# PowerPCB.net
KiCad netlist of a schematic drawn in Altium Designer
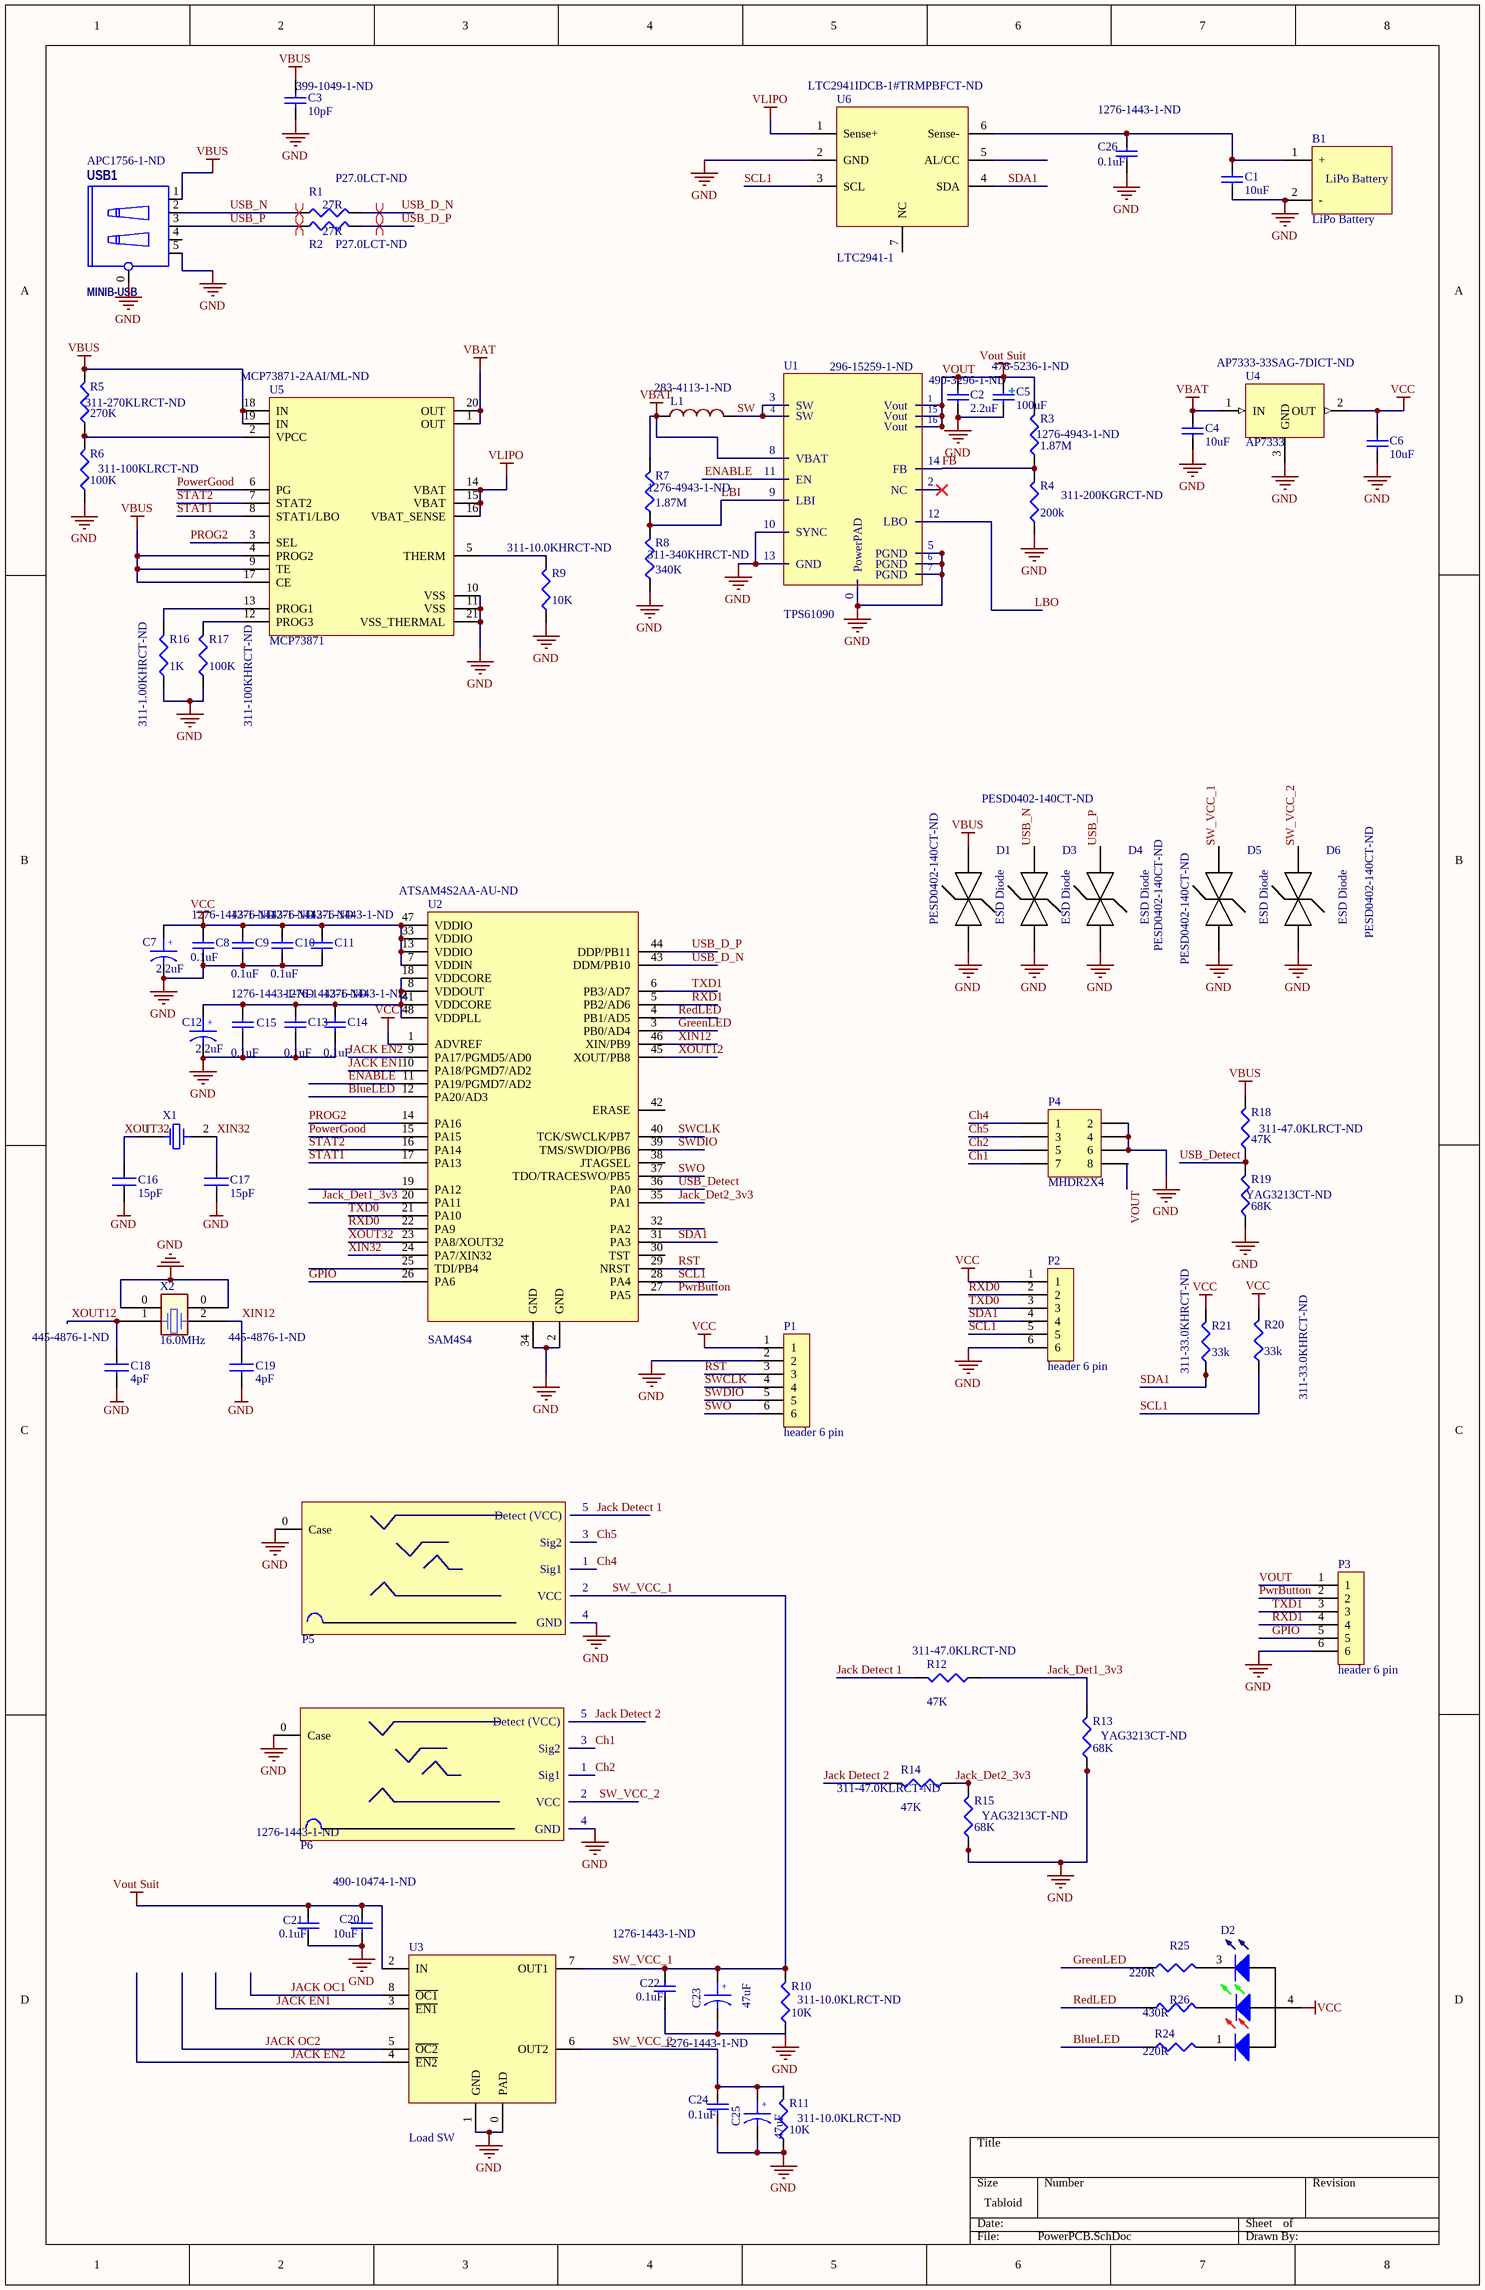
[diagram p0: PowerPCB.SchDoc]

(export (version "E")
  (design (tool "Eeschema 10.0.6"))
  (components
    (comp (ref "B1")
      (value "LiPo Battery")
      (footprint "LiPo Battery")
      (libsource (lib "SenaCorpLibSCH") (part "LiPo Battery"))
    )
    (comp (ref "C1")
      (value "10uF")
      (footprint "0603_small")
      (fields
        (field (name "MANUFACTURER PART NUMBER") "GRM188R61C106MA73D")
        (field (name "MANUFACTURER") "Murata Electronics North America")
        (field (name "TOLERANCE") "±20%")
      )
      (libsource (lib "SenaCorpLibSCH") (part "Cap"))
    )
    (comp (ref "C2")
      (value "2.2uF")
      (footprint "0603_small")
      (fields
        (field (name "SUPPLIER PART NUMBER") "490-3296-1-ND")
        (field (name "MANUFACTURER") "Murata Electronics North America")
        (field (name "TOLERANCE") "±10%")
        (field (name "MANUFACTURER PART NUMBER") "GRM188R61C225KE15D")
      )
      (libsource (lib "SenaCorpLibSCH") (part "Cap"))
    )
    (comp (ref "C3")
      (value "10pF")
      (footprint "0603_small")
      (fields
        (field (name "MANUFACTURER PART NUMBER") "C0603C100J5GACTU")
        (field (name "SUPPLIER PART NUMBER") "399-1049-1-ND")
      )
      (libsource (lib "SenaCorpLibSCH") (part "Cap"))
    )
    (comp (ref "C4")
      (value "10uF")
      (footprint "0603_small")
      (fields
        (field (name "MANUFACTURER PART NUMBER") "GRM188R61C106MA73D")
        (field (name "MANUFACTURER") "Murata Electronics North America")
        (field (name "TOLERANCE") "±20%")
      )
      (libsource (lib "SenaCorpLibSCH") (part "Cap"))
    )
    (comp (ref "C5")
      (value "100uF")
      (footprint "C 6032-28R")
      (description "Capacitor")
      (fields
        (field (name "MANUFACTURER PART NUMBER") "TPSC107M010R0075")
        (field (name "MANUFACTURER") "AVX Corporation")
        (field (name "SUPPLIER PART NUMBER") "478-5236-1-ND")
      )
      (libsource (lib "SenaCorpLibSCH") (part "Cap_Tant"))
    )
    (comp (ref "C6")
      (value "10uF")
      (footprint "0603_small")
      (fields
        (field (name "MANUFACTURER PART NUMBER") "GRM188R61C106MA73D")
        (field (name "MANUFACTURER") "Murata Electronics North America")
        (field (name "TOLERANCE") "±20%")
      )
      (libsource (lib "SenaCorpLibSCH") (part "Cap"))
    )
    (comp (ref "C7")
      (value "2.2uF")
      (footprint "SMD0805")
      (fields
        (field (name "TOLERANCE") "±20%")
        (field (name "MANUFACTURER") "AVX Corporation")
        (field (name "MANUFACTURER PART NUMBER") "F921A225MPA")
      )
      (libsource (lib "AltiumDbLib") (part "CAP-POL"))
    )
    (comp (ref "C8")
      (value "0.1uF")
      (footprint "0402")
      (description "Capacitor")
      (fields
        (field (name "SUPPLIER PART NUMBER") "1276-1443-1-ND")
        (field (name "MANUFACTURER PART NUMBER") "CL05A104MP5NNNC")
        (field (name "TOLERANCE") "±20%")
      )
      (libsource (lib "SenaCorpLibSCH") (part "Cap"))
    )
    (comp (ref "C9")
      (value "0.1uF")
      (footprint "0402")
      (description "Capacitor")
      (fields
        (field (name "SUPPLIER PART NUMBER") "1276-1443-1-ND")
        (field (name "MANUFACTURER PART NUMBER") "CL05A104MP5NNNC")
        (field (name "TOLERANCE") "±20%")
      )
      (libsource (lib "SenaCorpLibSCH") (part "Cap"))
    )
    (comp (ref "C10")
      (value "0.1uF")
      (footprint "0402")
      (description "Capacitor")
      (fields
        (field (name "SUPPLIER PART NUMBER") "1276-1443-1-ND")
        (field (name "MANUFACTURER PART NUMBER") "CL05A104MP5NNNC")
        (field (name "TOLERANCE") "±20%")
      )
      (libsource (lib "SenaCorpLibSCH") (part "Cap"))
    )
    (comp (ref "C11")
      (value "~")
      (footprint "0402")
      (description "Capacitor")
      (fields
        (field (name "SUPPLIER PART NUMBER") "1276-1443-1-ND")
        (field (name "MANUFACTURER PART NUMBER") "CL05A104MP5NNNC")
        (field (name "TOLERANCE") "±20%")
      )
      (libsource (lib "SenaCorpLibSCH") (part "Cap"))
    )
    (comp (ref "C12")
      (value "2.2uF")
      (footprint "SMD0805")
      (fields
        (field (name "TOLERANCE") "±20%")
        (field (name "MANUFACTURER") "AVX Corporation")
        (field (name "MANUFACTURER PART NUMBER") "F921A225MPA")
      )
      (libsource (lib "AltiumDbLib") (part "CAP-POL"))
    )
    (comp (ref "C13")
      (value "0.1uF")
      (footprint "0402")
      (description "Capacitor")
      (fields
        (field (name "SUPPLIER PART NUMBER") "1276-1443-1-ND")
        (field (name "MANUFACTURER PART NUMBER") "CL05A104MP5NNNC")
        (field (name "TOLERANCE") "±20%")
      )
      (libsource (lib "SenaCorpLibSCH") (part "Cap"))
    )
    (comp (ref "C14")
      (value "0.1uF")
      (footprint "0402")
      (description "Capacitor")
      (fields
        (field (name "SUPPLIER PART NUMBER") "1276-1443-1-ND")
        (field (name "MANUFACTURER PART NUMBER") "CL05A104MP5NNNC")
        (field (name "TOLERANCE") "±20%")
      )
      (libsource (lib "SenaCorpLibSCH") (part "Cap"))
    )
    (comp (ref "C15")
      (value "0.1uF")
      (footprint "0402")
      (description "Capacitor")
      (fields
        (field (name "SUPPLIER PART NUMBER") "1276-1443-1-ND")
        (field (name "MANUFACTURER PART NUMBER") "CL05A104MP5NNNC")
        (field (name "TOLERANCE") "±20%")
      )
      (libsource (lib "SenaCorpLibSCH") (part "Cap"))
    )
    (comp (ref "C16")
      (value "15pF")
      (footprint "CAP 0402")
      (fields
        (field (name "TOLERANCE") "±5%")
        (field (name "MANUFACTURER PART NUMBER") "GJM1555C1H150JB01D")
        (field (name "MANUFACTURER") "Murata Electronics North America")
      )
      (libsource (lib "AltiumDbLib") (part "CAP-NONPOL"))
    )
    (comp (ref "C17")
      (value "15pF")
      (footprint "CAP 0402")
      (fields
        (field (name "TOLERANCE") "±5%")
        (field (name "MANUFACTURER PART NUMBER") "GJM1555C1H150JB01D")
        (field (name "MANUFACTURER") "Murata Electronics North America")
      )
      (libsource (lib "AltiumDbLib") (part "CAP-NONPOL"))
    )
    (comp (ref "C18")
      (value "4pF")
      (footprint "0402")
      (fields
        (field (name "MANUFACTURER PART NUMBER") "C1005C0G1H040B050BA")
        (field (name "MANUFACTURER") "TDK Corporation")
        (field (name "SUPPLIER PART NUMBER") "445-4876-1-ND")
        (field (name "TOLERANCE") "±0.1pF")
      )
      (libsource (lib "AltiumDbLib") (part "CAP-NONPOL"))
    )
    (comp (ref "C19")
      (value "4pF")
      (footprint "0402")
      (fields
        (field (name "MANUFACTURER PART NUMBER") "C1005C0G1H040B050BA")
        (field (name "MANUFACTURER") "TDK Corporation")
        (field (name "SUPPLIER PART NUMBER") "445-4876-1-ND")
        (field (name "TOLERANCE") "±0.1pF")
      )
      (libsource (lib "AltiumDbLib") (part "CAP-NONPOL"))
    )
    (comp (ref "C20")
      (value "10uF")
      (footprint "0603_small")
      (fields
        (field (name "MANUFACTURER") "Murata Electronics North America")
        (field (name "MANUFACTURER PART NUMBER") "GRM188R61A106KE69D")
        (field (name "TOLERANCE") "±10%")
        (field (name "SUPPLIER PART NUMBER") "490-10474-1-ND")
      )
      (libsource (lib "SenaCorpLibSCH") (part "Cap"))
    )
    (comp (ref "C21")
      (value "0.1uF")
      (footprint "0402")
      (fields
        (field (name "SUPPLIER PART NUMBER") "1276-1443-1-ND")
        (field (name "MANUFACTURER PART NUMBER") "CL05A104MP5NNNC")
        (field (name "TOLERANCE") "±20%")
        (field (name "MANUFACTURER") "Samsung Electro-Mechanics America, Inc.")
      )
      (libsource (lib "SenaCorpLibSCH") (part "Cap"))
    )
    (comp (ref "C22")
      (value "0.1uF")
      (footprint "0402")
      (fields
        (field (name "SUPPLIER PART NUMBER") "1276-1443-1-ND")
        (field (name "MANUFACTURER PART NUMBER") "CL05A104MP5NNNC")
        (field (name "TOLERANCE") "±20%")
        (field (name "MANUFACTURER") "Samsung Electro-Mechanics America, Inc.")
      )
      (libsource (lib "SenaCorpLibSCH") (part "Cap"))
    )
    (comp (ref "C23")
      (value "47uF")
      (footprint "1206")
      (fields
        (field (name "MANUFACTURER PART NUMBER") "TPSB476K010R0250")
        (field (name "MANUFACTURER") "AVX Corporation")
        (field (name "TOLERANCE") "±10%")
      )
      (libsource (lib "AltiumDbLib") (part "CAP-POL"))
    )
    (comp (ref "C24")
      (value "0.1uF")
      (footprint "0402")
      (fields
        (field (name "SUPPLIER PART NUMBER") "1276-1443-1-ND")
        (field (name "MANUFACTURER PART NUMBER") "CL05A104MP5NNNC")
        (field (name "TOLERANCE") "±20%")
        (field (name "MANUFACTURER") "Samsung Electro-Mechanics America, Inc.")
      )
      (libsource (lib "SenaCorpLibSCH") (part "Cap"))
    )
    (comp (ref "C25")
      (value "47uF")
      (footprint "1206")
      (fields
        (field (name "MANUFACTURER PART NUMBER") "TPSB476K010R0250")
        (field (name "MANUFACTURER") "AVX Corporation")
        (field (name "TOLERANCE") "±10%")
      )
      (libsource (lib "AltiumDbLib") (part "CAP-POL"))
    )
    (comp (ref "C26")
      (value "0.1uF")
      (footprint "0402")
      (fields
        (field (name "SUPPLIER PART NUMBER") "1276-1443-1-ND")
        (field (name "MANUFACTURER PART NUMBER") "CL05A104MP5NNNC")
        (field (name "TOLERANCE") "±20%")
        (field (name "MANUFACTURER") "Samsung Electro-Mechanics America, Inc.")
      )
      (libsource (lib "SenaCorpLibSCH") (part "Cap"))
    )
    (comp (ref "D1")
      (value "ESD Diode")
      (footprint "0402")
      (fields
        (field (name "MANUFACTURER PART NUMBER") "PESD0402-140")
        (field (name "MANUFACTURER") "TE Connectivity Raychem Circuit Protection")
        (field (name "SUPPLIER PART NUMBER") "PESD0402-140CT-ND")
      )
      (libsource (lib "SenaCorpLibSCH") (part "ESD Diode"))
    )
    (comp (ref "D2")
      (value "LED2_RGB")
      (footprint "LED RGB")
      (description "RGB Led")
      (fields
        (field (name "MANUFACTURER PART NUMBER") "LTST-C19HE1WT")
        (field (name "MANUFACTURER") "Lite-On Inc")
      )
      (libsource (lib "SenaCorpLibSCH") (part "LED2_RGB"))
    )
    (comp (ref "D3")
      (value "ESD Diode")
      (footprint "0402")
      (fields
        (field (name "MANUFACTURER PART NUMBER") "PESD0402-140")
        (field (name "MANUFACTURER") "TE Connectivity Raychem Circuit Protection")
        (field (name "SUPPLIER PART NUMBER") "PESD0402-140CT-ND")
      )
      (libsource (lib "SenaCorpLibSCH") (part "ESD Diode"))
    )
    (comp (ref "D4")
      (value "ESD Diode")
      (footprint "0402")
      (fields
        (field (name "MANUFACTURER PART NUMBER") "PESD0402-140")
        (field (name "MANUFACTURER") "TE Connectivity Raychem Circuit Protection")
        (field (name "SUPPLIER PART NUMBER") "PESD0402-140CT-ND")
      )
      (libsource (lib "SenaCorpLibSCH") (part "ESD Diode"))
    )
    (comp (ref "D5")
      (value "ESD Diode")
      (footprint "0402")
      (fields
        (field (name "SUPPLIER PART NUMBER 1") "PESD0402-140CT-ND")
        (field (name "MANUFACTURER PART NUMBER") "PESD0402-140")
        (field (name "MANUFACTURER") "TE Connectivity Raychem Circuit Protection")
      )
      (libsource (lib "SenaCorpLibSCH") (part "ESD Diode"))
    )
    (comp (ref "D6")
      (value "ESD Diode")
      (footprint "0402")
      (fields
        (field (name "MANUFACTURER PART NUMBER") "PESD0402-140")
        (field (name "MANUFACTURER") "TE Connectivity Raychem Circuit Protection")
        (field (name "SUPPLIER PART NUMBER") "PESD0402-140CT-ND")
      )
      (libsource (lib "SenaCorpLibSCH") (part "ESD Diode"))
    )
    (comp (ref "L1")
      (value "6.8uH")
      (footprint "Inductor - Small")
      (description "Inductor")
      (fields
        (field (name "SUPPLIER PART NUMBER") "283-4113-1-ND")
        (field (name "MANUFACTURER PART NUMBER") "MPI4040R4-6R8-R")
        (field (name "TOLERANCE") "±20%")
      )
      (libsource (lib "SenaCorpLibSCH") (part "L6.2uH"))
    )
    (comp (ref "P1")
      (value "header 6 pin")
      (footprint "Header 6 1.27mm")
      (libsource (lib "SenaCorpLibSCH") (part "header 6 pin"))
    )
    (comp (ref "P2")
      (value "header 6 pin")
      (footprint "Header 6 1.27mm")
      (libsource (lib "SenaCorpLibSCH") (part "header 6 pin"))
    )
    (comp (ref "P3")
      (value "header 6 pin")
      (footprint "Header 6 1.27mm")
      (libsource (lib "SenaCorpLibSCH") (part "header 6 pin"))
    )
    (comp (ref "P4")
      (value "MHDR2X4")
      (footprint "MHDR2X4")
      (description "Header, 4-Pin, Dual row")
      (fields (field (name "PUBLISHER") "Altium Limited"))
      (libsource (lib "Miscellaneous Connectors") (part "MHDR2X4"))
    )
    (comp (ref "P5")
      (value "IP67_Jack")
      (footprint "AudioJack IPX7")
      (description "IP67 4 pole jack")
      (fields (field (name "MANUFACTURER PART NUMBER") "LGY2109-4900F") (field (name "MANUFACTURER") "SMK"))
      (libsource (lib "SenaCorpLibSCH") (part "IP67_Jack"))
    )
    (comp (ref "P6")
      (value "IP67_Jack")
      (footprint "AudioJack IPX7")
      (description "IP67 4 pole jack")
      (fields (field (name "MANUFACTURER PART NUMBER") "LGY2109-4900F") (field (name "MANUFACTURER") "SMK"))
      (libsource (lib "SenaCorpLibSCH") (part "IP67_Jack"))
    )
    (comp (ref "R1")
      (value "27R")
      (footprint "0402")
      (description "Resistor")
      (fields
        (field (name "MANUFACTURER PART NUMBER") "ERJ-2RKF27R0X")
        (field (name "MANUFACTURER") "Panasonic Electronic Components")
        (field (name "SUPPLIER PART NUMBER") "P27.0LCT-ND")
      )
      (libsource (lib "SenaCorpLibSCH") (part "Res3"))
    )
    (comp (ref "R2")
      (value "27R")
      (footprint "0402")
      (description "Resistor")
      (fields
        (field (name "MANUFACTURER PART NUMBER") "ERJ-2RKF27R0X")
        (field (name "MANUFACTURER") "Panasonic Electronic Components")
        (field (name "SUPPLIER PART NUMBER") "P27.0LCT-ND")
      )
      (libsource (lib "SenaCorpLibSCH") (part "Res3"))
    )
    (comp (ref "R3")
      (value "1.87M")
      (footprint "0603_small")
      (fields
        (field (name "MANUFACTURER PART NUMBER") "RC1608F1874CS")
        (field (name "TOLERANCE") "±1%")
        (field (name "MANUFACTURER") "Samsung Electro-Mechanics America, Inc.")
        (field (name "SUPPLIER PART NUMBER") "1276-4943-1-ND")
      )
      (libsource (lib "SenaCorpLibSCH") (part "Res3"))
    )
    (comp (ref "R4")
      (value "200k")
      (footprint "0603_small")
      (fields
        (field (name "MANUFACTURER") "Yageo")
        (field (name "MANUFACTURER PART NUMBER") "RC0603JR-07200KL")
        (field (name "SUPPLIER PART NUMBER") "311-200KGRCT-ND")
        (field (name "TOLERANCE") "±5%")
      )
      (libsource (lib "SenaCorpLibSCH") (part "Res3"))
    )
    (comp (ref "R5")
      (value "270K")
      (footprint "0402")
      (fields
        (field (name "TOLERANCE") "±1%")
        (field (name "SUPPLIER PART NUMBER") "311-270KLRCT-ND")
        (field (name "MANUFACTURER PART NUMBER") "RC0402FR-07270KL")
        (field (name "MANUFACTURER") "Yageo")
      )
      (libsource (lib "SenaCorpLibSCH") (part "Res3"))
    )
    (comp (ref "R6")
      (value "100K")
      (footprint "0402")
      (description "Resistor")
      (fields
        (field (name "MANUFACTURER PART NUMBER") "RC0402FR-07100KL")
        (field (name "MANUFACTURER") "Yageo")
        (field (name "SUPPLIER PART NUMBER") "311-100KLRCT-ND")
      )
      (libsource (lib "SenaCorpLibSCH") (part "Res3"))
    )
    (comp (ref "R7")
      (value "1.87M")
      (footprint "0603_small")
      (fields
        (field (name "MANUFACTURER PART NUMBER") "RC1608F1874CS")
        (field (name "TOLERANCE") "±1%")
        (field (name "MANUFACTURER") "Samsung Electro-Mechanics America, Inc.")
        (field (name "SUPPLIER PART NUMBER") "1276-4943-1-ND")
      )
      (libsource (lib "SenaCorpLibSCH") (part "Res3"))
    )
    (comp (ref "R8")
      (value "340K")
      (footprint "0603_small")
      (description "Resistor")
      (fields
        (field (name "MANUFACTURER PART NUMBER") "RC0603FR-07340KL")
        (field (name "SUPPLIER PART NUMBER") "311-340KHRCT-ND")
        (field (name "MANUFACTURER") "Yageo")
      )
      (libsource (lib "SenaCorpLibSCH") (part "Res3"))
    )
    (comp (ref "R9")
      (value "10K")
      (footprint "0603_small")
      (fields
        (field (name "MANUFACTURER PART NUMBER") "RC0603FR-0710KL")
        (field (name "SUPPLIER PART NUMBER") "311-10.0KHRCT-ND")
        (field (name "TOLERANCE") "±1%")
        (field (name "MANUFACTURER") "Yageo")
      )
      (libsource (lib "SenaCorpLibSCH") (part "Res3"))
    )
    (comp (ref "R10")
      (value "10K")
      (footprint "0402")
      (description "Resistor")
      (fields
        (field (name "TOLERANCE") "±1%")
        (field (name "SUPPLIER PART NUMBER") "311-10.0KLRCT-ND")
        (field (name "MANUFACTURER PART NUMBER") "RC0402FR-0710KL")
      )
      (libsource (lib "SenaCorpLibSCH") (part "Res3"))
    )
    (comp (ref "R11")
      (value "10K")
      (footprint "0402")
      (description "Resistor")
      (fields
        (field (name "TOLERANCE") "±1%")
        (field (name "SUPPLIER PART NUMBER") "311-10.0KLRCT-ND")
        (field (name "MANUFACTURER PART NUMBER") "RC0402FR-0710KL")
      )
      (libsource (lib "SenaCorpLibSCH") (part "Res3"))
    )
    (comp (ref "R12")
      (value "47K")
      (footprint "0402")
      (fields
        (field (name "SUPPLIER PART NUMBER") "311-47.0KLRCT-ND")
        (field (name "TOLERANCE") "±1%")
        (field (name "MANUFACTURER PART NUMBER") "RC0402FR-0747KL")
        (field (name "MANUFACTURER") "Yageo")
      )
      (libsource (lib "SenaCorpLibSCH") (part "Res3"))
    )
    (comp (ref "R13")
      (value "68K")
      (footprint "0402")
      (description "Resistor")
      (fields
        (field (name "TOLERANCE") "±1%")
        (field (name "MANUFACTURER PART NUMBER") "RC0402FR-0768K1L")
        (field (name "SUPPLIER PART NUMBER") "YAG3213CT-ND")
      )
      (libsource (lib "SenaCorpLibSCH") (part "Res3"))
    )
    (comp (ref "R14")
      (value "47K")
      (footprint "0402")
      (fields
        (field (name "SUPPLIER PART NUMBER") "311-47.0KLRCT-ND")
        (field (name "TOLERANCE") "±1%")
        (field (name "MANUFACTURER PART NUMBER") "RC0402FR-0747KL")
        (field (name "MANUFACTURER") "Yageo")
      )
      (libsource (lib "SenaCorpLibSCH") (part "Res3"))
    )
    (comp (ref "R15")
      (value "68K")
      (footprint "0402")
      (description "Resistor")
      (fields
        (field (name "TOLERANCE") "±1%")
        (field (name "MANUFACTURER PART NUMBER") "RC0402FR-0768K1L")
        (field (name "SUPPLIER PART NUMBER") "YAG3213CT-ND")
      )
      (libsource (lib "SenaCorpLibSCH") (part "Res3"))
    )
    (comp (ref "R16")
      (value "1K")
      (footprint "0603_small")
      (fields
        (field (name "TOLERANCE") "±1%")
        (field (name "MANUFACTURER") "Yageo")
        (field (name "SUPPLIER PART NUMBER") "311-1.00KHRCT-ND")
        (field (name "MANUFACTURER PART NUMBER") "RC0603FR-071KL")
      )
      (libsource (lib "SenaCorpLibSCH") (part "Res3"))
    )
    (comp (ref "R17")
      (value "100K")
      (footprint "0603_small")
      (fields
        (field (name "SUPPLIER PART NUMBER") "311-100KHRCT-ND")
        (field (name "MANUFACTURER PART NUMBER") "RC0603FR-07100KL")
        (field (name "TOLERANCE") "±1%")
        (field (name "MANUFACTURER") "Yageo")
      )
      (libsource (lib "SenaCorpLibSCH") (part "Res3"))
    )
    (comp (ref "R18")
      (value "47K")
      (footprint "0402")
      (fields
        (field (name "SUPPLIER PART NUMBER") "311-47.0KLRCT-ND")
        (field (name "TOLERANCE") "±1%")
        (field (name "MANUFACTURER PART NUMBER") "RC0402FR-0747KL")
        (field (name "MANUFACTURER") "Yageo")
      )
      (libsource (lib "SenaCorpLibSCH") (part "Res3"))
    )
    (comp (ref "R19")
      (value "68K")
      (footprint "0402")
      (description "Resistor")
      (fields
        (field (name "TOLERANCE") "±1%")
        (field (name "MANUFACTURER PART NUMBER") "RC0402FR-0768K1L")
        (field (name "SUPPLIER PART NUMBER") "YAG3213CT-ND")
      )
      (libsource (lib "SenaCorpLibSCH") (part "Res3"))
    )
    (comp (ref "R20")
      (value "33k")
      (footprint "0603_small")
      (description "Resistor")
      (fields
        (field (name "MANUFACTURER PART NUMBER") "RC0603FR-0733KL")
        (field (name "TOLERANCE") "±1%")
        (field (name "SUPPLIER PART NUMBER") "311-33.0KHRCT-ND")
      )
      (libsource (lib "SenaCorpLibSCH") (part "Res3"))
    )
    (comp (ref "R21")
      (value "33k")
      (footprint "0603_small")
      (fields
        (field (name "MANUFACTURER PART NUMBER") "RC0603FR-0733KL")
        (field (name "TOLERANCE") "±1%")
        (field (name "SUPPLIER PART NUMBER") "311-33.0KHRCT-ND")
        (field (name "MANUFACTURER") "Yageo")
      )
      (libsource (lib "SenaCorpLibSCH") (part "Res3"))
    )
    (comp (ref "R24")
      (value "220R")
      (footprint "0603_small")
      (description "Resistor")
      (fields (field (name "MANUFACTURER PART NUMBER") "ESR03EZPJ221") (field (name "TOLERANCE") "±5%"))
      (libsource (lib "SenaCorpLibSCH") (part "Res3"))
    )
    (comp (ref "R25")
      (value "220R")
      (footprint "0603_small")
      (description "Resistor")
      (fields (field (name "MANUFACTURER PART NUMBER") "ESR03EZPJ221") (field (name "TOLERANCE") "±5%"))
      (libsource (lib "SenaCorpLibSCH") (part "Res3"))
    )
    (comp (ref "R26")
      (value "430R")
      (footprint "0603_small")
      (description "Resistor")
      (fields (field (name "MANUFACTURER PART NUMBER") "ESR03EZPJ431") (field (name "TOLERANCE") "±5%"))
      (libsource (lib "SenaCorpLibSCH") (part "Res3"))
    )
    (comp (ref "U1")
      (value "TPS61090")
      (footprint "QFN 16 PQFN VQFN PVQFN 16 RSA")
      (description "Synchronous Boost Converter With 2-A Switch")
      (fields
        (field (name "SUPPLIER PART NUMBER") "296-15259-1-ND")
        (field (name "MANUFACTURER PART NUMBER") "TPS61090RSAR")
        (field (name "MANUFACTURER") "Texas Instruments")
      )
      (libsource (lib "SenaCorpLibSCH") (part "TPS61090"))
    )
    (comp (ref "U2")
      (value "SAM4S4")
      (footprint "QFP48")
      (fields
        (field (name "SUPPLIER PART NUMBER 1") "ATSAM4S2AA-AU-ND")
        (field (name "MANUFACTURER PART NUMBER") "ATSAM4S2AA-AU")
        (field (name "MANUFACTURER") "Atmel")
      )
      (libsource (lib "SenaCorpLibSCH") (part "SAM4S4"))
    )
    (comp (ref "U3")
      (value "Load SW")
      (footprint "SON8_0.65MM")
      (description "CURRENT-LIMITED, POWER-DISTRIBUTION SWITCHES")
      (fields
        (field (name "MANUFACTURER PART NUMBER") "TPS2042BDR")
        (field (name "MANUFACTURER") "Texas Instruments")
      )
      (libsource (lib "SenaCorpLibSCH") (part "TPS2042"))
    )
    (comp (ref "U4")
      (value "AP7333")
      (footprint "SOT23-3")
      (description "3.3 V regulator")
      (fields
        (field (name "SUPPLIER PART NUMBER 1") "AP7333-33SAG-7DICT-ND")
        (field (name "MANUFACTURER") "Diodes Incorporated")
        (field (name "MANUFACTURER PART NUMBER") "AP7333-33SAG-7")
      )
      (libsource (lib "SenaCorpLibSCH") (part "AP7333"))
    )
    (comp (ref "U5")
      (value "MCP73871")
      (footprint "QFN20")
      (fields
        (field (name "SUPPLIER PART NUMBER 1") "MCP73871-2AAI/ML-ND")
        (field (name "MANUFACTURER") "Microchip Technology")
        (field (name "MANUFACTURER PART NUMBER") "MCP73871-2AAI/ML")
      )
      (libsource (lib "SenaCorpLibSCH") (part "MCP73871"))
    )
    (comp (ref "U6")
      (value "LTC2941-1")
      (footprint "QFN6")
      (fields
        (field (name "SUPPLIER PART NUMBER 1") "LTC2941IDCB-1#TRMPBFCT-ND")
        (field (name "MANUFACTURER") "Linear Technology")
        (field (name "MANUFACTURER PART NUMBER") "LTC2941IDCB-1#TRMPBF")
      )
      (libsource (lib "SenaCorpLibSCH") (part "LTC2941-1"))
    )
    (comp (ref "USB1")
      (value "MINIB-USB")
      (footprint "Micro USB IP67")
      (fields
        (field (name "DIGIKEYPARTNUMBER") "H2959TR-ND")
        (field (name "MANUFACTURER") "Amphenol PCD")
        (field (name "SUPPLIER PART NUMBER") "APC1756-1-ND")
        (field (name "MANUFACTURER PART NUMBER") "MUC-20PFFR-JS8C01")
      )
      (libsource (lib "SenaCorpLibSCH") (part "CON-USB_1"))
    )
    (comp (ref "X1")
      (value "Xtal 32")
      (footprint "Xtal smd 32khz - larger")
      (fields
        (field (name "MANUFACTURER PART NUMBER") "ST3215SB32768E0HPWBB")
        (field (name "MANUFACTURER") "AVX Corp/Kyocera Corp")
      )
      (libsource (lib "SenaCorpLibSCH") (part "Xtal 32"))
    )
    (comp (ref "X2")
      (value "16.0MHz")
      (footprint "Xtal smd 3.2X2.5")
      (fields
        (field (name "MANUFACTURER PART NUMBER") "CX3225CA16000H0HSSCC")
        (field (name "MANUFACTURER") "AVX Corp/Kyocera Corp")
        (field (name "Comment") "Xtal 16")
      )
      (libsource (lib "SenaCorpLibSCH") (part "Xtal 12"))
    )
  )
  (nets
    (net (code "1") (name "/BlueLED") (class "Default")
      (node (ref "R24") (pin "1") (pinfunction "1_1") (pintype "passive"))
      (node (ref "U2") (pin "12") (pinfunction "PA20/AD3_12") (pintype "passive"))
    )
    (net (code "2") (name "/Ch1") (class "Default")
      (node (ref "P4") (pin "7") (pinfunction "7_7") (pintype "passive"))
      (node (ref "P6") (pin "3") (pinfunction "Sig2_3") (pintype "passive"))
    )
    (net (code "3") (name "/Ch2") (class "Default")
      (node (ref "P4") (pin "5") (pinfunction "5_5") (pintype "passive"))
      (node (ref "P6") (pin "1") (pinfunction "Sig1_1") (pintype "passive"))
    )
    (net (code "4") (name "/Ch4") (class "Default")
      (node (ref "P4") (pin "1") (pinfunction "1_1") (pintype "passive"))
      (node (ref "P5") (pin "1") (pinfunction "Sig1_1") (pintype "passive"))
    )
    (net (code "5") (name "/Ch5") (class "Default")
      (node (ref "P4") (pin "3") (pinfunction "3_3") (pintype "passive"))
      (node (ref "P5") (pin "3") (pinfunction "Sig2_3") (pintype "passive"))
    )
    (net (code "6") (name "/ENABLE") (class "Default")
      (node (ref "U1") (pin "11") (pinfunction "EN_11") (pintype "passive"))
      (node (ref "U2") (pin "11") (pinfunction "PA19/PGMD7/AD2_11") (pintype "passive"))
    )
    (net (code "7") (name "/FB") (class "Default")
      (node (ref "R3") (pin "1") (pinfunction "1_1") (pintype "passive"))
      (node (ref "R4") (pin "2") (pinfunction "2_2") (pintype "passive"))
      (node (ref "U1") (pin "14") (pinfunction "FB_14") (pintype "passive"))
    )
    (net (code "8") (name "/GPIO") (class "Default")
      (node (ref "P3") (pin "5") (pinfunction "5_5") (pintype "passive"))
      (node (ref "U2") (pin "26") (pinfunction "PA6_26") (pintype "passive"))
    )
    (net (code "9") (name "/GreenLED") (class "Default")
      (node (ref "R25") (pin "1") (pinfunction "1_1") (pintype "passive"))
      (node (ref "U2") (pin "3") (pinfunction "PB0/AD4_3") (pintype "passive"))
    )
    (net (code "10") (name "/JACK EN1") (class "Default")
      (node (ref "U2") (pin "10") (pinfunction "PA18/PGMD7/AD2_10") (pintype "passive"))
      (node (ref "U3") (pin "3") (pinfunction "~{EN1}_3") (pintype "passive"))
    )
    (net (code "11") (name "/JACK EN2") (class "Default")
      (node (ref "U2") (pin "9") (pinfunction "PA17/PGMD5/AD0_9") (pintype "passive"))
      (node (ref "U3") (pin "4") (pinfunction "~{EN2}_4") (pintype "passive"))
    )
    (net (code "12") (name "/JACK OC1") (class "Default")
      (node (ref "U3") (pin "8") (pinfunction "~{OC1}_8") (pintype "passive"))
    )
    (net (code "13") (name "/JACK OC2") (class "Default")
      (node (ref "U3") (pin "5") (pinfunction "~{OC2}_5") (pintype "passive"))
    )
    (net (code "14") (name "/Jack Detect 1") (class "Default")
      (node (ref "P5") (pin "5") (pinfunction "Detect_(VCC)_5") (pintype "passive"))
      (node (ref "R12") (pin "2") (pinfunction "2_2") (pintype "passive"))
    )
    (net (code "15") (name "/Jack Detect 2") (class "Default")
      (node (ref "P6") (pin "5") (pinfunction "Detect_(VCC)_5") (pintype "passive"))
      (node (ref "R14") (pin "2") (pinfunction "2_2") (pintype "passive"))
    )
    (net (code "16") (name "/Jack_Det1_3v3") (class "Default")
      (node (ref "R12") (pin "1") (pinfunction "1_1") (pintype "passive"))
      (node (ref "R13") (pin "2") (pinfunction "2_2") (pintype "passive"))
      (node (ref "U2") (pin "20") (pinfunction "PA11_20") (pintype "passive"))
    )
    (net (code "17") (name "/Jack_Det2_3v3") (class "Default")
      (node (ref "R14") (pin "1") (pinfunction "1_1") (pintype "passive"))
      (node (ref "R15") (pin "2") (pinfunction "2_2") (pintype "passive"))
      (node (ref "U2") (pin "35") (pinfunction "PA1_35") (pintype "passive"))
    )
    (net (code "18") (name "/LBI") (class "Default")
      (node (ref "R7") (pin "1") (pinfunction "1_1") (pintype "passive"))
      (node (ref "R8") (pin "2") (pinfunction "2_2") (pintype "passive"))
      (node (ref "U1") (pin "9") (pinfunction "LBI_9") (pintype "passive"))
    )
    (net (code "19") (name "/LBO") (class "Default")
      (node (ref "U1") (pin "12") (pinfunction "LBO_12") (pintype "passive"))
    )
    (net (code "20") (name "/PROG2") (class "Default")
      (node (ref "U2") (pin "14") (pinfunction "PA16_14") (pintype "passive"))
      (node (ref "U5") (pin "3") (pinfunction "SEL_3") (pintype "passive"))
    )
    (net (code "21") (name "/PowerGood") (class "Default")
      (node (ref "U2") (pin "15") (pinfunction "PA15_15") (pintype "passive"))
      (node (ref "U5") (pin "6") (pinfunction "PG_6") (pintype "passive"))
    )
    (net (code "22") (name "/PwrButton") (class "Default")
      (node (ref "P3") (pin "2") (pinfunction "2_2") (pintype "passive"))
      (node (ref "U2") (pin "27") (pinfunction "PA5_27") (pintype "passive"))
    )
    (net (code "23") (name "/RST") (class "Default")
      (node (ref "P1") (pin "3") (pinfunction "3_3") (pintype "passive"))
      (node (ref "U2") (pin "29") (pinfunction "NRST_29") (pintype "passive"))
    )
    (net (code "24") (name "/RXD0") (class "Default")
      (node (ref "P2") (pin "2") (pinfunction "2_2") (pintype "passive"))
      (node (ref "U2") (pin "22") (pinfunction "PA9_22") (pintype "passive"))
    )
    (net (code "25") (name "/RXD1") (class "Default")
      (node (ref "P3") (pin "4") (pinfunction "4_4") (pintype "passive"))
      (node (ref "U2") (pin "5") (pinfunction "PB2/AD6_5") (pintype "passive"))
    )
    (net (code "26") (name "/RedLED") (class "Default")
      (node (ref "R26") (pin "1") (pinfunction "1_1") (pintype "passive"))
      (node (ref "U2") (pin "4") (pinfunction "PB1/AD5_4") (pintype "passive"))
    )
    (net (code "27") (name "/SCL1") (class "Default")
      (node (ref "P2") (pin "5") (pinfunction "5_5") (pintype "passive"))
      (node (ref "R20") (pin "1") (pinfunction "1_1") (pintype "passive"))
      (node (ref "U2") (pin "28") (pinfunction "PA4_28") (pintype "passive"))
      (node (ref "U6") (pin "3") (pinfunction "SCL_3") (pintype "passive"))
    )
    (net (code "28") (name "/SDA1") (class "Default")
      (node (ref "P2") (pin "4") (pinfunction "4_4") (pintype "passive"))
      (node (ref "R21") (pin "1") (pinfunction "1_1") (pintype "passive"))
      (node (ref "U2") (pin "31") (pinfunction "PA3_31") (pintype "passive"))
      (node (ref "U6") (pin "4") (pinfunction "SDA_4") (pintype "passive"))
    )
    (net (code "29") (name "/STAT1") (class "Default")
      (node (ref "U2") (pin "17") (pinfunction "PA13_17") (pintype "passive"))
      (node (ref "U5") (pin "8") (pinfunction "STAT1/LBO_8") (pintype "passive"))
    )
    (net (code "30") (name "/STAT2") (class "Default")
      (node (ref "U2") (pin "16") (pinfunction "PA14_16") (pintype "passive"))
      (node (ref "U5") (pin "7") (pinfunction "STAT2_7") (pintype "passive"))
    )
    (net (code "31") (name "/SW") (class "Default")
      (node (ref "L1") (pin "2") (pinfunction "2_2") (pintype "passive"))
      (node (ref "U1") (pin "3") (pinfunction "SW_3") (pintype "passive"))
      (node (ref "U1") (pin "4") (pinfunction "SW_4") (pintype "passive"))
    )
    (net (code "32") (name "/SWCLK") (class "Default")
      (node (ref "P1") (pin "4") (pinfunction "4_4") (pintype "passive"))
      (node (ref "U2") (pin "40") (pinfunction "TCK/SWCLK/PB7_40") (pintype "passive"))
    )
    (net (code "33") (name "/SWDIO") (class "Default")
      (node (ref "P1") (pin "5") (pinfunction "5_5") (pintype "passive"))
      (node (ref "U2") (pin "39") (pinfunction "TMS/SWDIO/PB6_39") (pintype "passive"))
    )
    (net (code "34") (name "/SWO") (class "Default")
      (node (ref "P1") (pin "6") (pinfunction "6_6") (pintype "passive"))
      (node (ref "U2") (pin "37") (pinfunction "TDO/TRACESWO/PB5_37") (pintype "passive"))
    )
    (net (code "35") (name "/SW_VCC_1") (class "Default")
      (node (ref "C22") (pin "1") (pinfunction "1_1") (pintype "passive"))
      (node (ref "C23") (pin "1") (pinfunction "1_1") (pintype "passive"))
      (node (ref "D5") (pin "1") (pinfunction "1_1") (pintype "passive"))
      (node (ref "P5") (pin "2") (pinfunction "VCC_2") (pintype "passive"))
      (node (ref "R10") (pin "2") (pinfunction "2_2") (pintype "passive"))
      (node (ref "U3") (pin "7") (pinfunction "OUT1_7") (pintype "passive"))
    )
    (net (code "36") (name "/SW_VCC_2") (class "Default")
      (node (ref "C24") (pin "1") (pinfunction "1_1") (pintype "passive"))
      (node (ref "C25") (pin "1") (pinfunction "1_1") (pintype "passive"))
      (node (ref "D6") (pin "1") (pinfunction "1_1") (pintype "passive"))
      (node (ref "P6") (pin "2") (pinfunction "VCC_2") (pintype "passive"))
      (node (ref "R11") (pin "2") (pinfunction "2_2") (pintype "passive"))
      (node (ref "U3") (pin "6") (pinfunction "OUT2_6") (pintype "passive"))
    )
    (net (code "37") (name "/TXD0") (class "Default")
      (node (ref "P2") (pin "3") (pinfunction "3_3") (pintype "passive"))
      (node (ref "U2") (pin "21") (pinfunction "PA10_21") (pintype "passive"))
    )
    (net (code "38") (name "/TXD1") (class "Default")
      (node (ref "P3") (pin "3") (pinfunction "3_3") (pintype "passive"))
      (node (ref "U2") (pin "6") (pinfunction "PB3/AD7_6") (pintype "passive"))
    )
    (net (code "39") (name "/USB_D_N") (class "Default")
      (node (ref "R1") (pin "2") (pinfunction "2_2") (pintype "passive"))
      (node (ref "U2") (pin "43") (pinfunction "DDM/PB10_43") (pintype "passive"))
    )
    (net (code "40") (name "/USB_D_P") (class "Default")
      (node (ref "R2") (pin "2") (pinfunction "2_2") (pintype "passive"))
      (node (ref "U2") (pin "44") (pinfunction "DDP/PB11_44") (pintype "passive"))
    )
    (net (code "41") (name "/USB_Detect") (class "Default")
      (node (ref "R18") (pin "1") (pinfunction "1_1") (pintype "passive"))
      (node (ref "R19") (pin "2") (pinfunction "2_2") (pintype "passive"))
      (node (ref "U2") (pin "36") (pinfunction "PA0_36") (pintype "passive"))
    )
    (net (code "42") (name "/USB_N") (class "Default")
      (node (ref "D3") (pin "1") (pinfunction "1_1") (pintype "passive"))
      (node (ref "R1") (pin "1") (pinfunction "1_1") (pintype "passive"))
      (node (ref "USB1") (pin "2") (pinfunction "2_2") (pintype "passive"))
    )
    (net (code "43") (name "/USB_P") (class "Default")
      (node (ref "D4") (pin "1") (pinfunction "1_1") (pintype "passive"))
      (node (ref "R2") (pin "1") (pinfunction "1_1") (pintype "passive"))
      (node (ref "USB1") (pin "3") (pinfunction "3_3") (pintype "passive"))
    )
    (net (code "44") (name "/XIN12") (class "Default")
      (node (ref "C19") (pin "1") (pinfunction "1_1") (pintype "passive"))
      (node (ref "U2") (pin "46") (pinfunction "XIN/PB9_46") (pintype "passive"))
      (node (ref "X2") (pin "2") (pinfunction "2_2") (pintype "passive"))
    )
    (net (code "45") (name "/XIN32") (class "Default")
      (node (ref "C17") (pin "1") (pinfunction "1_1") (pintype "passive"))
      (node (ref "U2") (pin "24") (pinfunction "PA7/XIN32_24") (pintype "passive"))
      (node (ref "X1") (pin "2") (pinfunction "2_2") (pintype "passive"))
    )
    (net (code "46") (name "/XOUT12") (class "Default")
      (node (ref "C18") (pin "1") (pinfunction "1_1") (pintype "passive"))
      (node (ref "U2") (pin "45") (pinfunction "XOUT/PB8_45") (pintype "passive"))
      (node (ref "X2") (pin "1") (pinfunction "1_1") (pintype "passive"))
    )
    (net (code "47") (name "/XOUT32") (class "Default")
      (node (ref "C16") (pin "1") (pinfunction "1_1") (pintype "passive"))
      (node (ref "U2") (pin "23") (pinfunction "PA8/XOUT32_23") (pintype "passive"))
      (node (ref "X1") (pin "1") (pinfunction "1_1") (pintype "passive"))
    )
    (net (code "48") (name "GND") (class "Default")
      (node (ref "B1") (pin "2") (pinfunction "-_2") (pintype "passive"))
      (node (ref "C1") (pin "1") (pinfunction "1_1") (pintype "passive"))
      (node (ref "C10") (pin "1") (pinfunction "1_1") (pintype "passive"))
      (node (ref "C11") (pin "1") (pinfunction "1_1") (pintype "passive"))
      (node (ref "C12") (pin "2") (pinfunction "2_2") (pintype "passive"))
      (node (ref "C13") (pin "1") (pinfunction "1_1") (pintype "passive"))
      (node (ref "C14") (pin "1") (pinfunction "1_1") (pintype "passive"))
      (node (ref "C15") (pin "1") (pinfunction "1_1") (pintype "passive"))
      (node (ref "C16") (pin "2") (pinfunction "2_2") (pintype "passive"))
      (node (ref "C17") (pin "2") (pinfunction "2_2") (pintype "passive"))
      (node (ref "C18") (pin "2") (pinfunction "2_2") (pintype "passive"))
      (node (ref "C19") (pin "2") (pinfunction "2_2") (pintype "passive"))
      (node (ref "C2") (pin "1") (pinfunction "1_1") (pintype "passive"))
      (node (ref "C20") (pin "2") (pinfunction "2_2") (pintype "passive"))
      (node (ref "C21") (pin "2") (pinfunction "2_2") (pintype "passive"))
      (node (ref "C22") (pin "2") (pinfunction "2_2") (pintype "passive"))
      (node (ref "C23") (pin "2") (pinfunction "2_2") (pintype "passive"))
      (node (ref "C24") (pin "2") (pinfunction "2_2") (pintype "passive"))
      (node (ref "C25") (pin "2") (pinfunction "2_2") (pintype "passive"))
      (node (ref "C26") (pin "2") (pinfunction "2_2") (pintype "passive"))
      (node (ref "C3") (pin "1") (pinfunction "1_1") (pintype "passive"))
      (node (ref "C4") (pin "1") (pinfunction "1_1") (pintype "passive"))
      (node (ref "C5") (pin "-") (pinfunction "-_-") (pintype "passive"))
      (node (ref "C6") (pin "1") (pinfunction "1_1") (pintype "passive"))
      (node (ref "C7") (pin "2") (pinfunction "2_2") (pintype "passive"))
      (node (ref "C8") (pin "1") (pinfunction "1_1") (pintype "passive"))
      (node (ref "C9") (pin "1") (pinfunction "1_1") (pintype "passive"))
      (node (ref "D1") (pin "2") (pinfunction "2_2") (pintype "passive"))
      (node (ref "D3") (pin "2") (pinfunction "2_2") (pintype "passive"))
      (node (ref "D4") (pin "2") (pinfunction "2_2") (pintype "passive"))
      (node (ref "D5") (pin "2") (pinfunction "2_2") (pintype "passive"))
      (node (ref "D6") (pin "2") (pinfunction "2_2") (pintype "passive"))
      (node (ref "P1") (pin "2") (pinfunction "2_2") (pintype "passive"))
      (node (ref "P2") (pin "6") (pinfunction "6_6") (pintype "passive"))
      (node (ref "P3") (pin "6") (pinfunction "6_6") (pintype "passive"))
      (node (ref "P4") (pin "2") (pinfunction "2_2") (pintype "passive"))
      (node (ref "P4") (pin "4") (pinfunction "4_4") (pintype "passive"))
      (node (ref "P4") (pin "6") (pinfunction "6_6") (pintype "passive"))
      (node (ref "P5") (pin "0") (pinfunction "Case_0") (pintype "passive"))
      (node (ref "P5") (pin "4") (pinfunction "GND_4") (pintype "passive"))
      (node (ref "P6") (pin "0") (pinfunction "Case_0") (pintype "passive"))
      (node (ref "P6") (pin "4") (pinfunction "GND_4") (pintype "passive"))
      (node (ref "R11") (pin "1") (pinfunction "1_1") (pintype "passive"))
      (node (ref "R13") (pin "1") (pinfunction "1_1") (pintype "passive"))
      (node (ref "R15") (pin "1") (pinfunction "1_1") (pintype "passive"))
      (node (ref "R16") (pin "1") (pinfunction "1_1") (pintype "passive"))
      (node (ref "R17") (pin "1") (pinfunction "1_1") (pintype "passive"))
      (node (ref "R19") (pin "1") (pinfunction "1_1") (pintype "passive"))
      (node (ref "R4") (pin "1") (pinfunction "1_1") (pintype "passive"))
      (node (ref "R6") (pin "1") (pinfunction "1_1") (pintype "passive"))
      (node (ref "R8") (pin "1") (pinfunction "1_1") (pintype "passive"))
      (node (ref "R9") (pin "1") (pinfunction "1_1") (pintype "passive"))
      (node (ref "U1") (pin "0") (pinfunction "PowerPAD_0") (pintype "passive"))
      (node (ref "U1") (pin "10") (pinfunction "SYNC_10") (pintype "passive"))
      (node (ref "U1") (pin "13") (pinfunction "GND_13") (pintype "passive"))
      (node (ref "U1") (pin "5") (pinfunction "PGND_5") (pintype "passive"))
      (node (ref "U1") (pin "6") (pinfunction "PGND_6") (pintype "passive"))
      (node (ref "U1") (pin "7") (pinfunction "PGND_7") (pintype "passive"))
      (node (ref "U2") (pin "2") (pinfunction "GND_2") (pintype "passive"))
      (node (ref "U2") (pin "34") (pinfunction "GND_34") (pintype "passive"))
      (node (ref "U3") (pin "0") (pinfunction "PAD_0") (pintype "passive"))
      (node (ref "U3") (pin "1") (pinfunction "GND_1") (pintype "passive"))
      (node (ref "U4") (pin "3") (pinfunction "GND_3") (pintype "passive"))
      (node (ref "U5") (pin "10") (pinfunction "VSS_10") (pintype "passive"))
      (node (ref "U5") (pin "11") (pinfunction "VSS_11") (pintype "passive"))
      (node (ref "U5") (pin "21") (pinfunction "VSS_THERMAL_21") (pintype "passive"))
      (node (ref "U6") (pin "2") (pinfunction "GND_2") (pintype "passive"))
      (node (ref "USB1") (pin "0") (pinfunction "GND_0") (pintype "passive"))
      (node (ref "USB1") (pin "5") (pinfunction "5_5") (pintype "passive"))
      (node (ref "X2") (pin "0") (pinfunction "0_0") (pintype "passive"))
    )
    (net (code "49") (name "Net-(B1-+)") (class "Default")
      (node (ref "B1") (pin "1") (pinfunction "+_1") (pintype "passive"))
      (node (ref "C1") (pin "2") (pinfunction "2_2") (pintype "passive"))
      (node (ref "C26") (pin "1") (pinfunction "1_1") (pintype "passive"))
      (node (ref "U6") (pin "6") (pinfunction "Sense-_6") (pintype "passive"))
    )
    (net (code "50") (name "Net-(D2-Pad1)") (class "Default")
      (node (ref "D2") (pin "1") (pinfunction "1_1") (pintype "passive"))
      (node (ref "R24") (pin "2") (pinfunction "2_2") (pintype "passive"))
    )
    (net (code "51") (name "Net-(D2-Pad2)") (class "Default")
      (node (ref "D2") (pin "2") (pinfunction "2_2") (pintype "passive"))
      (node (ref "R26") (pin "2") (pinfunction "2_2") (pintype "passive"))
    )
    (net (code "52") (name "Net-(D2-Pad3)") (class "Default")
      (node (ref "D2") (pin "3") (pinfunction "3_3") (pintype "passive"))
      (node (ref "R25") (pin "2") (pinfunction "2_2") (pintype "passive"))
    )
    (net (code "53") (name "Net-(U2-VDDOUT)") (class "Default")
      (node (ref "C12") (pin "1") (pinfunction "1_1") (pintype "passive"))
      (node (ref "C13") (pin "2") (pinfunction "2_2") (pintype "passive"))
      (node (ref "C14") (pin "2") (pinfunction "2_2") (pintype "passive"))
      (node (ref "C15") (pin "2") (pinfunction "2_2") (pintype "passive"))
      (node (ref "U2") (pin "18") (pinfunction "VDDCORE_18") (pintype "passive"))
      (node (ref "U2") (pin "41") (pinfunction "VDDCORE_41") (pintype "passive"))
      (node (ref "U2") (pin "48") (pinfunction "VDDPLL_48") (pintype "passive"))
      (node (ref "U2") (pin "8") (pinfunction "VDDOUT_8") (pintype "passive"))
    )
    (net (code "54") (name "Net-(U5-PROG1)") (class "Default")
      (node (ref "R16") (pin "2") (pinfunction "2_2") (pintype "passive"))
      (node (ref "U5") (pin "13") (pinfunction "PROG1_13") (pintype "passive"))
    )
    (net (code "55") (name "Net-(U5-PROG3)") (class "Default")
      (node (ref "R17") (pin "2") (pinfunction "2_2") (pintype "passive"))
      (node (ref "U5") (pin "12") (pinfunction "PROG3_12") (pintype "passive"))
    )
    (net (code "56") (name "Net-(U5-THERM)") (class "Default")
      (node (ref "R9") (pin "2") (pinfunction "2_2") (pintype "passive"))
      (node (ref "U5") (pin "5") (pinfunction "THERM_5") (pintype "passive"))
    )
    (net (code "57") (name "Net-(U5-VPCC)") (class "Default")
      (node (ref "R5") (pin "1") (pinfunction "1_1") (pintype "passive"))
      (node (ref "R6") (pin "2") (pinfunction "2_2") (pintype "passive"))
      (node (ref "U5") (pin "2") (pinfunction "VPCC_2") (pintype "passive"))
    )
    (net (code "58") (name "VBAT") (class "Default")
      (node (ref "C4") (pin "2") (pinfunction "2_2") (pintype "passive"))
      (node (ref "L1") (pin "1") (pinfunction "1_1") (pintype "passive"))
      (node (ref "R7") (pin "2") (pinfunction "2_2") (pintype "passive"))
      (node (ref "U1") (pin "8") (pinfunction "VBAT_8") (pintype "passive"))
      (node (ref "U4") (pin "1") (pinfunction "IN_1") (pintype "input"))
      (node (ref "U5") (pin "1") (pinfunction "OUT_1") (pintype "passive"))
      (node (ref "U5") (pin "20") (pinfunction "OUT_20") (pintype "passive"))
    )
    (net (code "59") (name "VBUS") (class "Default")
      (node (ref "C3") (pin "2") (pinfunction "2_2") (pintype "passive"))
      (node (ref "D1") (pin "1") (pinfunction "1_1") (pintype "passive"))
      (node (ref "R18") (pin "2") (pinfunction "2_2") (pintype "passive"))
      (node (ref "R5") (pin "2") (pinfunction "2_2") (pintype "passive"))
      (node (ref "U5") (pin "17") (pinfunction "CE_17") (pintype "passive"))
      (node (ref "U5") (pin "18") (pinfunction "IN_18") (pintype "passive"))
      (node (ref "U5") (pin "19") (pinfunction "IN_19") (pintype "passive"))
      (node (ref "U5") (pin "4") (pinfunction "PROG2_4") (pintype "passive"))
      (node (ref "U5") (pin "9") (pinfunction "TE_9") (pintype "passive"))
      (node (ref "USB1") (pin "1") (pinfunction "1_1") (pintype "passive"))
    )
    (net (code "60") (name "VCC") (class "Default")
      (node (ref "C10") (pin "2") (pinfunction "2_2") (pintype "passive"))
      (node (ref "C11") (pin "2") (pinfunction "2_2") (pintype "passive"))
      (node (ref "C6") (pin "2") (pinfunction "2_2") (pintype "passive"))
      (node (ref "C7") (pin "1") (pinfunction "1_1") (pintype "passive"))
      (node (ref "C8") (pin "2") (pinfunction "2_2") (pintype "passive"))
      (node (ref "C9") (pin "2") (pinfunction "2_2") (pintype "passive"))
      (node (ref "D2") (pin "4") (pinfunction "4_4") (pintype "passive"))
      (node (ref "P1") (pin "1") (pinfunction "1_1") (pintype "passive"))
      (node (ref "P2") (pin "1") (pinfunction "1_1") (pintype "passive"))
      (node (ref "R20") (pin "2") (pinfunction "2_2") (pintype "passive"))
      (node (ref "R21") (pin "2") (pinfunction "2_2") (pintype "passive"))
      (node (ref "U2") (pin "1") (pinfunction "ADVREF_1") (pintype "passive"))
      (node (ref "U2") (pin "13") (pinfunction "VDDIO_13") (pintype "passive"))
      (node (ref "U2") (pin "33") (pinfunction "VDDIO_33") (pintype "passive"))
      (node (ref "U2") (pin "47") (pinfunction "VDDIO_47") (pintype "passive"))
      (node (ref "U2") (pin "7") (pinfunction "VDDIN_7") (pintype "passive"))
      (node (ref "U4") (pin "2") (pinfunction "OUT_2") (pintype "output"))
    )
    (net (code "61") (name "VLIPO") (class "Default")
      (node (ref "U5") (pin "14") (pinfunction "VBAT_14") (pintype "passive"))
      (node (ref "U5") (pin "15") (pinfunction "VBAT_15") (pintype "passive"))
      (node (ref "U5") (pin "16") (pinfunction "VBAT_SENSE_16") (pintype "passive"))
      (node (ref "U6") (pin "1") (pinfunction "Sense+_1") (pintype "passive"))
    )
    (net (code "62") (name "Vout Suit") (class "Default")
      (node (ref "C2") (pin "2") (pinfunction "2_2") (pintype "passive"))
      (node (ref "C20") (pin "1") (pinfunction "1_1") (pintype "passive"))
      (node (ref "C21") (pin "1") (pinfunction "1_1") (pintype "passive"))
      (node (ref "C5") (pin "+") (pinfunction "+_+") (pintype "passive"))
      (node (ref "P3") (pin "1") (pinfunction "1_1") (pintype "passive"))
      (node (ref "P4") (pin "8") (pinfunction "8_8") (pintype "passive"))
      (node (ref "R3") (pin "2") (pinfunction "2_2") (pintype "passive"))
      (node (ref "U1") (pin "1") (pinfunction "Vout_1") (pintype "passive"))
      (node (ref "U1") (pin "15") (pinfunction "Vout_15") (pintype "passive"))
      (node (ref "U1") (pin "16") (pinfunction "Vout_16") (pintype "passive"))
      (node (ref "U3") (pin "2") (pinfunction "IN_2") (pintype "passive"))
    )
    (net (code "63") (name "unconnected-(R10-Pad1)") (class "Default")
      (node (ref "R10") (pin "1") (pinfunction "1_1") (pintype "passive"))
    )
    (net (code "64") (name "unconnected-(U1-NC-Pad2)") (class "Default")
      (node (ref "U1") (pin "2") (pinfunction "NC_2") (pintype "passive+no_connect"))
    )
    (net (code "65") (name "unconnected-(U2-ERASE-Pad42)") (class "Default")
      (node (ref "U2") (pin "42") (pinfunction "ERASE_42") (pintype "passive"))
    )
    (net (code "66") (name "unconnected-(U2-JTAGSEL-Pad38)") (class "Default")
      (node (ref "U2") (pin "38") (pinfunction "JTAGSEL_38") (pintype "passive"))
    )
    (net (code "67") (name "unconnected-(U2-PA2-Pad32)") (class "Default")
      (node (ref "U2") (pin "32") (pinfunction "PA2_32") (pintype "passive"))
    )
    (net (code "68") (name "unconnected-(U2-PA12-Pad19)") (class "Default")
      (node (ref "U2") (pin "19") (pinfunction "PA12_19") (pintype "passive"))
    )
    (net (code "69") (name "unconnected-(U2-TDI{slash}PB4-Pad25)") (class "Default")
      (node (ref "U2") (pin "25") (pinfunction "TDI/PB4_25") (pintype "passive"))
    )
    (net (code "70") (name "unconnected-(U2-TST-Pad30)") (class "Default")
      (node (ref "U2") (pin "30") (pinfunction "TST_30") (pintype "passive"))
    )
    (net (code "71") (name "unconnected-(U6-AL{slash}CC-Pad5)") (class "Default")
      (node (ref "U6") (pin "5") (pinfunction "AL/CC_5") (pintype "passive"))
    )
    (net (code "72") (name "unconnected-(U6-NC-Pad7)") (class "Default")
      (node (ref "U6") (pin "7") (pinfunction "NC_7") (pintype "passive"))
    )
    (net (code "73") (name "unconnected-(USB1-Pad4)") (class "Default")
      (node (ref "USB1") (pin "4") (pinfunction "4_4") (pintype "passive"))
    )
  )
)
